# circuitplay_rev_G.net
KiCad netlist of a schematic drawn in EAGLE
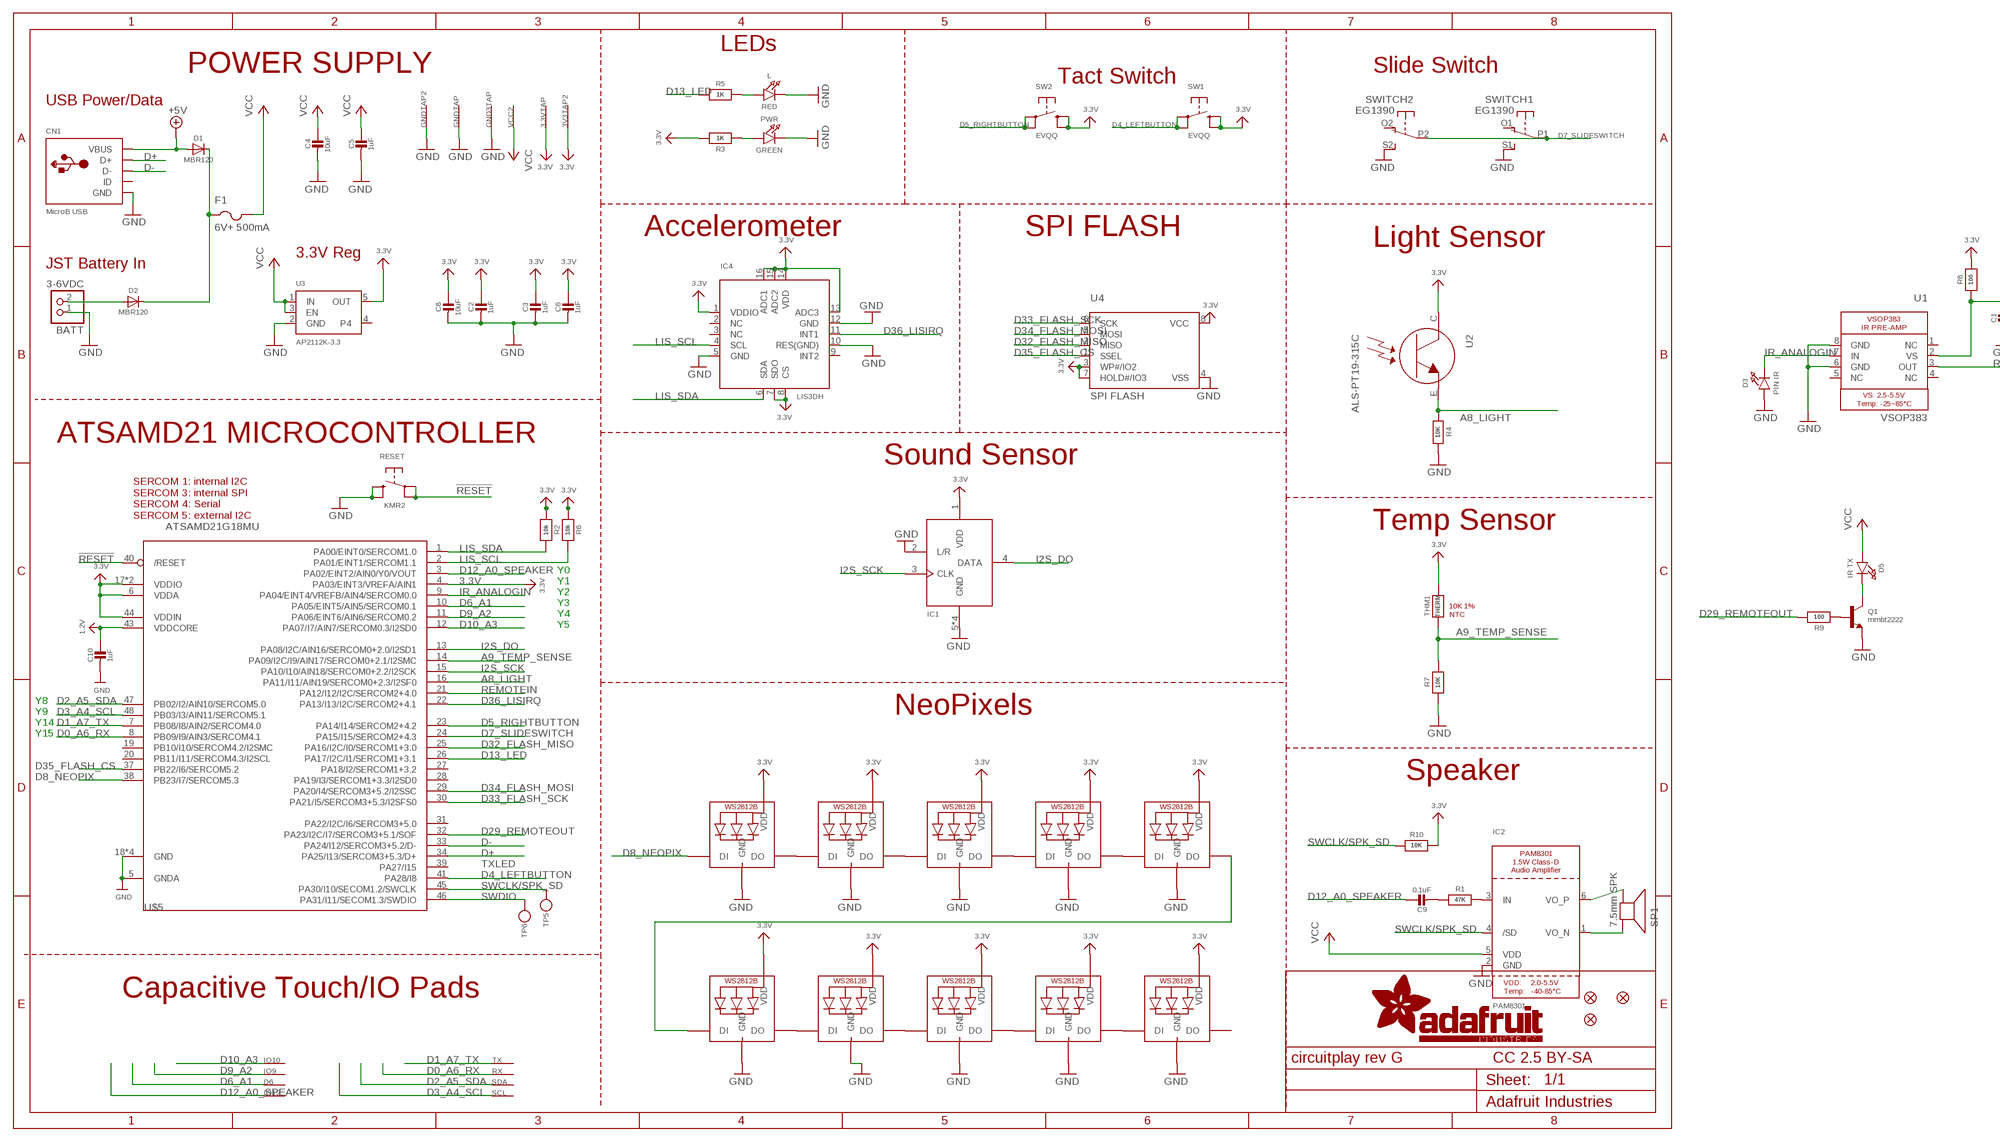
[diagram p0: schematic, sheet 1, part 1 of 2]
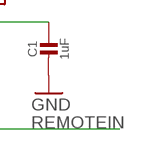
[diagram p1: schematic, sheet 1, part 2 of 2]

(export (version "E")
  (design (tool "Eeschema 10.0.6"))
  (components
    (comp (ref "3.3VTAP")
      (value "SEWTAP-ALLIGATOR")
      (footprint "eagle-import:SEWALLI")
      (libsource (lib "eagle-import") (part "SEWTAP-ALLIGATOR"))
    )
    (comp (ref "3V3TAP2")
      (value "SEWTAP-ALLIGATOR")
      (footprint "eagle-import:SEWALLI")
      (libsource (lib "eagle-import") (part "SEWTAP-ALLIGATOR"))
    )
    (comp (ref "BATT")
      (value "3-6VDC")
      (footprint "eagle-import:JSTPH2")
      (libsource (lib "eagle-import") (part "CON_JST_PH_2PIN"))
    )
    (comp (ref "C1")
      (value "1uF")
      (footprint "eagle-import:0603-NO")
      (libsource (lib "eagle-import") (part "CAP_CERAMIC0603_NO"))
    )
    (comp (ref "C2")
      (value "1uF")
      (footprint "eagle-import:0603-NO")
      (libsource (lib "eagle-import") (part "CAP_CERAMIC0603_NO"))
    )
    (comp (ref "C3")
      (value "1uF")
      (footprint "eagle-import:0603-NO")
      (libsource (lib "eagle-import") (part "CAP_CERAMIC0603_NO"))
    )
    (comp (ref "C4")
      (value "10uF")
      (footprint "eagle-import:0805-NO")
      (libsource (lib "eagle-import") (part "CAP_CERAMIC0805-NOOUTLINE"))
    )
    (comp (ref "C5")
      (value "1uF")
      (footprint "eagle-import:0603-NO")
      (libsource (lib "eagle-import") (part "CAP_CERAMIC0603_NO"))
    )
    (comp (ref "C6")
      (value "1uF")
      (footprint "eagle-import:0603-NO")
      (libsource (lib "eagle-import") (part "CAP_CERAMIC0603_NO"))
    )
    (comp (ref "C8")
      (value "10uF")
      (footprint "eagle-import:0805-NO")
      (libsource (lib "eagle-import") (part "CAP_CERAMIC0805-NOOUTLINE"))
    )
    (comp (ref "C9")
      (value "0.1uF")
      (footprint "eagle-import:0603-NO")
      (libsource (lib "eagle-import") (part "CAP_CERAMIC0603_NO"))
    )
    (comp (ref "C10")
      (value "1uF")
      (footprint "eagle-import:0603-NO")
      (libsource (lib "eagle-import") (part "CAP_CERAMIC0603_NO"))
    )
    (comp (ref "CN1")
      (value "MicroB USB")
      (footprint "eagle-import:4UCONN_20329_V2")
      (libsource (lib "eagle-import") (part "USB_MICRO_20329_V2"))
    )
    (comp (ref "D1")
      (value "MBR120")
      (footprint "eagle-import:SOD-123")
      (libsource (lib "eagle-import") (part "DIODESOD-123"))
    )
    (comp (ref "D2")
      (value "MBR120")
      (footprint "eagle-import:SOD-123")
      (libsource (lib "eagle-import") (part "DIODESOD-123"))
    )
    (comp (ref "D3")
      (value "PIN IR")
      (footprint "eagle-import:CHIPLED_1206_NOOUTLINE")
      (libsource (lib "eagle-import") (part "LED1206_NOOUTLINE"))
    )
    (comp (ref "D5")
      (value "IR TX")
      (footprint "eagle-import:CHIPLED_1206_NOOUTLINE")
      (libsource (lib "eagle-import") (part "LED1206_NOOUTLINE"))
    )
    (comp (ref "D6")
      (value "SEWTAP-ALLIGATOR")
      (footprint "eagle-import:SEWALLI")
      (libsource (lib "eagle-import") (part "SEWTAP-ALLIGATOR"))
    )
    (comp (ref "F1")
      (value "6V+ 500mA")
      (footprint "eagle-import:R1206")
      (libsource (lib "eagle-import") (part "PTCFUSE-1206"))
    )
    (comp (ref "GND3TAP")
      (value "SEWTAP-ALLIGATOR")
      (footprint "eagle-import:SEWALLI")
      (libsource (lib "eagle-import") (part "SEWTAP-ALLIGATOR"))
    )
    (comp (ref "GNDTAP")
      (value "SEWTAP-ALLIGATOR")
      (footprint "eagle-import:SEWALLI")
      (libsource (lib "eagle-import") (part "SEWTAP-ALLIGATOR"))
    )
    (comp (ref "GNDTAP2")
      (value "SEWTAP-ALLIGATOR")
      (footprint "eagle-import:SEWALLI")
      (libsource (lib "eagle-import") (part "SEWTAP-ALLIGATOR"))
    )
    (comp (ref "IC1")
      (value "MIC_PDM")
      (footprint "eagle-import:SPK0415HM4H")
      (libsource (lib "eagle-import") (part "MIC_PDM_SPK0415"))
    )
    (comp (ref "IC2")
      (value "PAM8301")
      (footprint "eagle-import:SOT23-6")
      (libsource (lib "eagle-import") (part "PAM8301"))
    )
    (comp (ref "IC4")
      (value "LIS3DH")
      (footprint "eagle-import:LGA16_3X3MM")
      (libsource (lib "eagle-import") (part "ACCEL_LIS3DHTR"))
    )
    (comp (ref "IO9")
      (value "SEWTAP-ALLIGATOR")
      (footprint "eagle-import:SEWALLI")
      (libsource (lib "eagle-import") (part "SEWTAP-ALLIGATOR"))
    )
    (comp (ref "IO10")
      (value "SEWTAP-ALLIGATOR")
      (footprint "eagle-import:SEWALLI")
      (libsource (lib "eagle-import") (part "SEWTAP-ALLIGATOR"))
    )
    (comp (ref "IO12")
      (value "SEWTAP-ALLIGATOR")
      (footprint "eagle-import:SEWALLI")
      (libsource (lib "eagle-import") (part "SEWTAP-ALLIGATOR"))
    )
    (comp (ref "L")
      (value "RED")
      (footprint "eagle-import:CHIPLED_0805_NOOUTLINE")
      (libsource (lib "eagle-import") (part "LED0805_NOOUTLINE"))
    )
    (comp (ref "LED1")
      (value "WS2812B3535")
      (footprint "eagle-import:LED3535")
      (libsource (lib "eagle-import") (part "WS2812B3535"))
    )
    (comp (ref "LED2")
      (value "WS2812B3535")
      (footprint "eagle-import:LED3535")
      (libsource (lib "eagle-import") (part "WS2812B3535"))
    )
    (comp (ref "LED3")
      (value "WS2812B3535")
      (footprint "eagle-import:LED3535")
      (libsource (lib "eagle-import") (part "WS2812B3535"))
    )
    (comp (ref "LED4")
      (value "WS2812B3535")
      (footprint "eagle-import:LED3535")
      (libsource (lib "eagle-import") (part "WS2812B3535"))
    )
    (comp (ref "LED5")
      (value "WS2812B3535")
      (footprint "eagle-import:LED3535")
      (libsource (lib "eagle-import") (part "WS2812B3535"))
    )
    (comp (ref "LED6")
      (value "WS2812B3535")
      (footprint "eagle-import:LED3535")
      (libsource (lib "eagle-import") (part "WS2812B3535"))
    )
    (comp (ref "LED7")
      (value "WS2812B3535")
      (footprint "eagle-import:LED3535")
      (libsource (lib "eagle-import") (part "WS2812B3535"))
    )
    (comp (ref "LED8")
      (value "WS2812B3535")
      (footprint "eagle-import:LED3535")
      (libsource (lib "eagle-import") (part "WS2812B3535"))
    )
    (comp (ref "LED9")
      (value "WS2812B3535")
      (footprint "eagle-import:LED3535")
      (libsource (lib "eagle-import") (part "WS2812B3535"))
    )
    (comp (ref "LED10")
      (value "WS2812B3535")
      (footprint "eagle-import:LED3535")
      (libsource (lib "eagle-import") (part "WS2812B3535"))
    )
    (comp (ref "PWR")
      (value "GREEN")
      (footprint "eagle-import:CHIPLED_0805_NOOUTLINE")
      (libsource (lib "eagle-import") (part "LED0805_NOOUTLINE"))
    )
    (comp (ref "Q1")
      (value "mmbt2222")
      (footprint "eagle-import:SOT23-R")
      (libsource (lib "eagle-import") (part "TRANSISTOR_NPN"))
    )
    (comp (ref "R1")
      (value "47K")
      (footprint "eagle-import:0603-NO")
      (libsource (lib "eagle-import") (part "RESISTOR_0603_NOOUT"))
    )
    (comp (ref "R2")
      (value "10k")
      (footprint "eagle-import:0603-NO")
      (libsource (lib "eagle-import") (part "RESISTOR_0603_NOOUT"))
    )
    (comp (ref "R3")
      (value "1K")
      (footprint "eagle-import:0603-NO")
      (libsource (lib "eagle-import") (part "RESISTOR_0603_NOOUT"))
    )
    (comp (ref "R4")
      (value "10K")
      (footprint "eagle-import:0603-NO")
      (libsource (lib "eagle-import") (part "RESISTOR_0603_NOOUT"))
    )
    (comp (ref "R5")
      (value "1K")
      (footprint "eagle-import:0603-NO")
      (libsource (lib "eagle-import") (part "RESISTOR_0603_NOOUT"))
    )
    (comp (ref "R6")
      (value "10k")
      (footprint "eagle-import:0603-NO")
      (libsource (lib "eagle-import") (part "RESISTOR_0603_NOOUT"))
    )
    (comp (ref "R7")
      (value "10K")
      (footprint "eagle-import:0603-NO")
      (libsource (lib "eagle-import") (part "RESISTOR_0603_NOOUT"))
    )
    (comp (ref "R8")
      (value "100")
      (footprint "eagle-import:0603-NO")
      (libsource (lib "eagle-import") (part "RESISTOR_0603_NOOUT"))
    )
    (comp (ref "R9")
      (value "100")
      (footprint "eagle-import:0603-NO")
      (libsource (lib "eagle-import") (part "RESISTOR_0603_NOOUT"))
    )
    (comp (ref "R10")
      (value "10K")
      (footprint "eagle-import:0603-NO")
      (libsource (lib "eagle-import") (part "RESISTOR_0603_NOOUT"))
    )
    (comp (ref "RESET")
      (value "KMR2")
      (footprint "eagle-import:BTN_KMR2_4.6X2.8")
      (libsource (lib "eagle-import") (part "SWITCH_TACT_SMT4.6X2.8"))
    )
    (comp (ref "RX")
      (value "SEWTAP-ALLIGATOR")
      (footprint "eagle-import:SEWALLI")
      (libsource (lib "eagle-import") (part "SEWTAP-ALLIGATOR"))
    )
    (comp (ref "SCL")
      (value "SEWTAP-ALLIGATOR")
      (footprint "eagle-import:SEWALLI")
      (libsource (lib "eagle-import") (part "SEWTAP-ALLIGATOR"))
    )
    (comp (ref "SDA")
      (value "SEWTAP-ALLIGATOR")
      (footprint "eagle-import:SEWALLI")
      (libsource (lib "eagle-import") (part "SEWTAP-ALLIGATOR"))
    )
    (comp (ref "SP1")
      (value "7.5mm SPK")
      (footprint "eagle-import:BUZZER_SMT_7.5MM")
      (libsource (lib "eagle-import") (part "SPEAKER_7.5MM"))
    )
    (comp (ref "SW1")
      (value "EVQQ")
      (footprint "eagle-import:EVQ-Q2_SMALLER")
      (libsource (lib "eagle-import") (part "SWITCH_TACT_SMT_EVQQ2_SMALL"))
    )
    (comp (ref "SW2")
      (value "EVQQ")
      (footprint "eagle-import:EVQ-Q2_SMALLER")
      (libsource (lib "eagle-import") (part "SWITCH_TACT_SMT_EVQQ2_SMALL"))
    )
    (comp (ref "SWITCH")
      (value "EG1390")
      (footprint "eagle-import:EG1390")
      (libsource (lib "eagle-import") (part "DPDT-EG1390"))
    )
    (comp (ref "THM1")
      (value "THERM")
      (footprint "eagle-import:_0402")
      (libsource (lib "eagle-import") (part "RESISTOR_0402"))
    )
    (comp (ref "TP5")
      (value "TESTPOINTROUND1.5MM")
      (footprint "eagle-import:TESTPOINT_ROUND_1.5MM")
      (libsource (lib "eagle-import") (part "TESTPOINTROUND1.5MM"))
    )
    (comp (ref "TP6")
      (value "TESTPOINTROUND1.5MM")
      (footprint "eagle-import:TESTPOINT_ROUND_1.5MM")
      (libsource (lib "eagle-import") (part "TESTPOINTROUND1.5MM"))
    )
    (comp (ref "TX")
      (value "SEWTAP-ALLIGATOR")
      (footprint "eagle-import:SEWALLI")
      (libsource (lib "eagle-import") (part "SEWTAP-ALLIGATOR"))
    )
    (comp (ref "U$2")
      (value "FIDUCIAL_1MM")
      (footprint "eagle-import:FIDUCIAL_1MM")
      (libsource (lib "eagle-import") (part "FIDUCIAL_1MM"))
    )
    (comp (ref "U$3")
      (value "FIDUCIAL_1MM")
      (footprint "eagle-import:FIDUCIAL_1MM")
      (fields (field (name "BOM") "EXCLUDE"))
      (libsource (lib "eagle-import") (part "FIDUCIAL_1MM"))
    )
    (comp (ref "U$5")
      (value "ATSAMD21G18MU")
      (footprint "eagle-import:TQFN48_7MM")
      (libsource (lib "eagle-import") (part "ATSAMD21G_QFN"))
    )
    (comp (ref "U$6")
      (value "FIDUCIAL_1MM")
      (footprint "eagle-import:FIDUCIAL_1MM")
      (libsource (lib "eagle-import") (part "FIDUCIAL_1MM"))
    )
    (comp (ref "U1")
      (value "VSOP383")
      (footprint "eagle-import:VSOP383")
      (libsource (lib "eagle-import") (part "VSOP383"))
    )
    (comp (ref "U2")
      (value "ALS-PT19-315C")
      (footprint "eagle-import:ALS-PT19-315C")
      (libsource (lib "eagle-import") (part "LIGHT_ALS-PT19-315C"))
    )
    (comp (ref "U3")
      (value "AP2112K-3.3")
      (footprint "eagle-import:SOT23-5")
      (libsource (lib "eagle-import") (part "VREG_SOT23-5"))
    )
    (comp (ref "U4")
      (value "SPI FLASH")
      (footprint "eagle-import:SOIC8_150MIL")
      (libsource (lib "eagle-import") (part "SPIFLASH_SOIC8"))
    )
    (comp (ref "VCC2")
      (value "SEWTAP-ALLIGATOR")
      (footprint "eagle-import:SEWALLI")
      (libsource (lib "eagle-import") (part "SEWTAP-ALLIGATOR"))
    )
  )
  (nets
    (net (code "1") (name "+5V") (class "Default")
      (node (ref "CN1") (pin "VBUS") (pinfunction "VBUS_VBUS") (pintype "power_in"))
      (node (ref "D1") (pin "A") (pinfunction "A_A") (pintype "passive"))
    )
    (net (code "2") (name "/A8_LIGHT") (class "Default")
      (node (ref "R4") (pin "2") (pinfunction "2_2") (pintype "passive"))
      (node (ref "U$5") (pin "16") (pinfunction "PA11/I11/AIN19/SERCOM0+2.3/I2SF0_16") (pintype "bidirectional"))
      (node (ref "U2") (pin "E") (pinfunction "E_E") (pintype "bidirectional"))
    )
    (net (code "3") (name "/A9_TEMP_SENSE") (class "Default")
      (node (ref "R7") (pin "2") (pinfunction "2_2") (pintype "passive"))
      (node (ref "THM1") (pin "1") (pinfunction "1_1") (pintype "passive"))
      (node (ref "U$5") (pin "14") (pinfunction "PA09/I2C/I9/AIN17/SERCOM0+2.1/I2SMC_14") (pintype "bidirectional"))
    )
    (net (code "4") (name "/D+") (class "Default")
      (node (ref "CN1") (pin "D+") (pinfunction "D+_D+") (pintype "bidirectional"))
      (node (ref "U$5") (pin "34") (pinfunction "PA25/I13/SERCOM3+5.3/D+_34") (pintype "bidirectional"))
    )
    (net (code "5") (name "/D-") (class "Default")
      (node (ref "CN1") (pin "D-") (pinfunction "D-_D-") (pintype "bidirectional"))
      (node (ref "U$5") (pin "33") (pinfunction "PA24/I12/SERCOM3+5.2/D-_33") (pintype "bidirectional"))
    )
    (net (code "6") (name "/D0_A6_RX") (class "Default")
      (node (ref "RX") (pin "P$1") (pinfunction "SEW_P$1") (pintype "bidirectional"))
      (node (ref "U$5") (pin "8") (pinfunction "PB09/I9/AIN3/SERCOM4.1_8") (pintype "bidirectional"))
    )
    (net (code "7") (name "/D1_A7_TX") (class "Default")
      (node (ref "TX") (pin "P$1") (pinfunction "SEW_P$1") (pintype "bidirectional"))
      (node (ref "U$5") (pin "7") (pinfunction "PB08/I8/AIN2/SERCOM4.0_7") (pintype "bidirectional"))
    )
    (net (code "8") (name "/D2_A5_SDA") (class "Default")
      (node (ref "SDA") (pin "P$1") (pinfunction "SEW_P$1") (pintype "bidirectional"))
      (node (ref "U$5") (pin "47") (pinfunction "PB02/I2/AIN10/SERCOM5.0_47") (pintype "bidirectional"))
    )
    (net (code "9") (name "/D3_A4_SCL") (class "Default")
      (node (ref "SCL") (pin "P$1") (pinfunction "SEW_P$1") (pintype "bidirectional"))
      (node (ref "U$5") (pin "48") (pinfunction "PB03/I3/AIN11/SERCOM5.1_48") (pintype "bidirectional"))
    )
    (net (code "10") (name "/D4_LEFTBUTTON") (class "Default")
      (node (ref "SW1") (pin "A") (pinfunction "P_A") (pintype "passive"))
      (node (ref "SW1") (pin "A'") (pinfunction "P1_A'") (pintype "passive"))
      (node (ref "U$5") (pin "41") (pinfunction "PA28/I8_41") (pintype "bidirectional"))
    )
    (net (code "11") (name "/D5_RIGHTBUTTON") (class "Default")
      (node (ref "SW2") (pin "A") (pinfunction "P_A") (pintype "passive"))
      (node (ref "SW2") (pin "A'") (pinfunction "P1_A'") (pintype "passive"))
      (node (ref "U$5") (pin "23") (pinfunction "PA14/I14/SERCOM2+4.2_23") (pintype "bidirectional"))
    )
    (net (code "12") (name "/D6_A1") (class "Default")
      (node (ref "D6") (pin "P$1") (pinfunction "SEW_P$1") (pintype "bidirectional"))
      (node (ref "U$5") (pin "10") (pinfunction "PA05/EINT5/AIN5/SERCOM0.1_10") (pintype "bidirectional"))
    )
    (net (code "13") (name "/D7_SLIDESWITCH") (class "Default")
      (node (ref "SWITCH") (pin "P1") (pinfunction "P_P1") (pintype "passive"))
      (node (ref "SWITCH") (pin "P2") (pinfunction "P_P2") (pintype "passive"))
      (node (ref "U$5") (pin "24") (pinfunction "PA15/I15/SERCOM2+4.3_24") (pintype "bidirectional"))
    )
    (net (code "14") (name "/D8_NEOPIX") (class "Default")
      (node (ref "LED6") (pin "1") (pinfunction "DI_1") (pintype "input"))
      (node (ref "U$5") (pin "38") (pinfunction "PB23/I7/SERCOM5.3_38") (pintype "bidirectional"))
    )
    (net (code "15") (name "/D9_A2") (class "Default")
      (node (ref "IO9") (pin "P$1") (pinfunction "SEW_P$1") (pintype "bidirectional"))
      (node (ref "U$5") (pin "11") (pinfunction "PA06/EINT6/AIN6/SERCOM0.2_11") (pintype "bidirectional"))
    )
    (net (code "16") (name "/D10_A3") (class "Default")
      (node (ref "IO10") (pin "P$1") (pinfunction "SEW_P$1") (pintype "bidirectional"))
      (node (ref "U$5") (pin "12") (pinfunction "PA07/I7/AIN7/SERCOM0.3/I2SD0_12") (pintype "bidirectional"))
    )
    (net (code "17") (name "/D12_A0_SPEAKER") (class "Default")
      (node (ref "C9") (pin "1") (pinfunction "1_1") (pintype "passive"))
      (node (ref "IO12") (pin "P$1") (pinfunction "SEW_P$1") (pintype "bidirectional"))
      (node (ref "U$5") (pin "3") (pinfunction "PA02/EINT2/AIN0/Y0/VOUT_3") (pintype "bidirectional"))
    )
    (net (code "18") (name "/D13_LED") (class "Default")
      (node (ref "R5") (pin "1") (pinfunction "1_1") (pintype "passive"))
      (node (ref "U$5") (pin "26") (pinfunction "PA17/I2C/I1/SERCOM1+3.1_26") (pintype "bidirectional"))
    )
    (net (code "19") (name "/D29_REMOTEOUT") (class "Default")
      (node (ref "R9") (pin "2") (pinfunction "2_2") (pintype "passive"))
      (node (ref "U$5") (pin "32") (pinfunction "PA23/I2C/I7/SERCOM3+5.1/SOF_32") (pintype "bidirectional"))
    )
    (net (code "20") (name "/D32_FLASH_MISO") (class "Default")
      (node (ref "U$5") (pin "25") (pinfunction "PA16/I2C/I0/SERCOM1+3.0_25") (pintype "bidirectional"))
      (node (ref "U4") (pin "2") (pinfunction "MISO_2") (pintype "bidirectional"))
    )
    (net (code "21") (name "/D33_FLASH_SCK") (class "Default")
      (node (ref "U$5") (pin "30") (pinfunction "PA21/I5/SERCOM3+5.3/I2SFS0_30") (pintype "bidirectional"))
      (node (ref "U4") (pin "6") (pinfunction "SCK_6") (pintype "bidirectional"))
    )
    (net (code "22") (name "/D34_FLASH_MOSI") (class "Default")
      (node (ref "U$5") (pin "29") (pinfunction "PA20/I4/SERCOM3+5.2/I2SSC_29") (pintype "bidirectional"))
      (node (ref "U4") (pin "5") (pinfunction "MOSI_5") (pintype "bidirectional"))
    )
    (net (code "23") (name "/D35_FLASH_CS") (class "Default")
      (node (ref "U$5") (pin "37") (pinfunction "PB22/I6/SERCOM5.2_37") (pintype "bidirectional"))
      (node (ref "U4") (pin "1") (pinfunction "SSEL_1") (pintype "bidirectional"))
    )
    (net (code "24") (name "/D36_LISIRQ") (class "Default")
      (node (ref "IC4") (pin "11") (pinfunction "INT1_11") (pintype "output"))
      (node (ref "U$5") (pin "22") (pinfunction "PA13/I13/I2C/SERCOM2+4.1_22") (pintype "bidirectional"))
    )
    (net (code "25") (name "/I2S_DO") (class "Default")
      (node (ref "IC1") (pin "4") (pinfunction "DATA_4") (pintype "bidirectional"))
      (node (ref "U$5") (pin "13") (pinfunction "PA08/I2C/AIN16/SERCOM0+2.0/I2SD1_13") (pintype "bidirectional"))
    )
    (net (code "26") (name "/I2S_SCK") (class "Default")
      (node (ref "IC1") (pin "3") (pinfunction "CLK_3") (pintype "input"))
      (node (ref "U$5") (pin "15") (pinfunction "PA10/I10/AIN18/SERCOM0+2.2/I2SCK_15") (pintype "bidirectional"))
    )
    (net (code "27") (name "/IR_ANALOGIN") (class "Default")
      (node (ref "D3") (pin "C") (pinfunction "C_C") (pintype "passive"))
      (node (ref "U$5") (pin "9") (pinfunction "PA04/EINT4/VREFB/AIN4/SERCOM0.0_9") (pintype "bidirectional"))
      (node (ref "U1") (pin "7") (pinfunction "IN_7") (pintype "input"))
    )
    (net (code "28") (name "/LIS_SCL") (class "Default")
      (node (ref "IC4") (pin "4") (pinfunction "SCL_4") (pintype "bidirectional"))
      (node (ref "R6") (pin "2") (pinfunction "2_2") (pintype "passive"))
      (node (ref "U$5") (pin "2") (pinfunction "PA01/EINT1/SERCOM1.1_2") (pintype "bidirectional"))
    )
    (net (code "29") (name "/LIS_SDA") (class "Default")
      (node (ref "IC4") (pin "6") (pinfunction "SDA_6") (pintype "bidirectional"))
      (node (ref "R2") (pin "2") (pinfunction "2_2") (pintype "passive"))
      (node (ref "U$5") (pin "1") (pinfunction "PA00/EINT0/SERCOM1.0_1") (pintype "bidirectional"))
    )
    (net (code "30") (name "/REMOTEIN") (class "Default")
      (node (ref "U$5") (pin "21") (pinfunction "PA12/I12/I2C/SERCOM2+4.0_21") (pintype "bidirectional"))
      (node (ref "U1") (pin "3") (pinfunction "OUT_3") (pintype "output"))
    )
    (net (code "31") (name "/SWCLK{slash}SPK_SD") (class "Default")
      (node (ref "IC2") (pin "4") (pinfunction "/SD_4") (pintype "input"))
      (node (ref "R10") (pin "1") (pinfunction "1_1") (pintype "passive"))
      (node (ref "TP5") (pin "P$1") (pinfunction "P$1_P$1") (pintype "bidirectional"))
      (node (ref "U$5") (pin "45") (pinfunction "PA30/I10/SECOM1.2/SWCLK_45") (pintype "bidirectional"))
    )
    (net (code "32") (name "/SWDIO") (class "Default")
      (node (ref "TP6") (pin "P$1") (pinfunction "P$1_P$1") (pintype "bidirectional"))
      (node (ref "U$5") (pin "46") (pinfunction "PA31/I11/SECOM1.3/SWDIO_46") (pintype "bidirectional"))
    )
    (net (code "33") (name "/~{RESET}") (class "Default")
      (node (ref "RESET") (pin "A") (pinfunction "P_A") (pintype "passive"))
      (node (ref "RESET") (pin "A'") (pinfunction "P1_A'") (pintype "passive"))
      (node (ref "U$5") (pin "40") (pinfunction "/RESET_40") (pintype "bidirectional"))
    )
    (net (code "34") (name "1.2V") (class "Default")
      (node (ref "C10") (pin "1") (pinfunction "1_1") (pintype "passive"))
      (node (ref "U$5") (pin "43") (pinfunction "VDDCORE_43") (pintype "power_in"))
    )
    (net (code "35") (name "3.3V") (class "Default")
      (node (ref "3.3VTAP") (pin "P$1") (pinfunction "SEW_P$1") (pintype "bidirectional"))
      (node (ref "3V3TAP2") (pin "P$1") (pinfunction "SEW_P$1") (pintype "bidirectional"))
      (node (ref "C2") (pin "1") (pinfunction "1_1") (pintype "passive"))
      (node (ref "C3") (pin "1") (pinfunction "1_1") (pintype "passive"))
      (node (ref "C6") (pin "1") (pinfunction "1_1") (pintype "passive"))
      (node (ref "C8") (pin "1") (pinfunction "1_1") (pintype "passive"))
      (node (ref "IC1") (pin "1") (pinfunction "VDD_1") (pintype "power_in"))
      (node (ref "IC4") (pin "1") (pinfunction "VDDIO_1") (pintype "power_in"))
      (node (ref "IC4") (pin "13") (pinfunction "ADC3_13") (pintype "input"))
      (node (ref "IC4") (pin "14") (pinfunction "VDD_14") (pintype "power_in"))
      (node (ref "IC4") (pin "15") (pinfunction "ADC2_15") (pintype "input"))
      (node (ref "IC4") (pin "16") (pinfunction "ADC1_16") (pintype "input"))
      (node (ref "IC4") (pin "7") (pinfunction "SDO_7") (pintype "bidirectional"))
      (node (ref "IC4") (pin "8") (pinfunction "CS_8") (pintype "input"))
      (node (ref "LED1") (pin "2") (pinfunction "VDD_2") (pintype "power_in"))
      (node (ref "LED10") (pin "2") (pinfunction "VDD_2") (pintype "power_in"))
      (node (ref "LED2") (pin "2") (pinfunction "VDD_2") (pintype "power_in"))
      (node (ref "LED3") (pin "2") (pinfunction "VDD_2") (pintype "power_in"))
      (node (ref "LED4") (pin "2") (pinfunction "VDD_2") (pintype "power_in"))
      (node (ref "LED5") (pin "2") (pinfunction "VDD_2") (pintype "power_in"))
      (node (ref "LED6") (pin "2") (pinfunction "VDD_2") (pintype "power_in"))
      (node (ref "LED7") (pin "2") (pinfunction "VDD_2") (pintype "power_in"))
      (node (ref "LED8") (pin "2") (pinfunction "VDD_2") (pintype "power_in"))
      (node (ref "LED9") (pin "2") (pinfunction "VDD_2") (pintype "power_in"))
      (node (ref "R10") (pin "2") (pinfunction "2_2") (pintype "passive"))
      (node (ref "R2") (pin "1") (pinfunction "1_1") (pintype "passive"))
      (node (ref "R3") (pin "2") (pinfunction "2_2") (pintype "passive"))
      (node (ref "R6") (pin "1") (pinfunction "1_1") (pintype "passive"))
      (node (ref "R8") (pin "2") (pinfunction "2_2") (pintype "passive"))
      (node (ref "SW1") (pin "B") (pinfunction "S_B") (pintype "passive"))
      (node (ref "SW1") (pin "B'") (pinfunction "S1_B'") (pintype "passive"))
      (node (ref "SW2") (pin "B") (pinfunction "S_B") (pintype "passive"))
      (node (ref "SW2") (pin "B'") (pinfunction "S1_B'") (pintype "passive"))
      (node (ref "THM1") (pin "2") (pinfunction "2_2") (pintype "passive"))
      (node (ref "U$5") (pin "17") (pinfunction "VDDIO_17") (pintype "power_in"))
      (node (ref "U$5") (pin "36") (pinfunction "VDDIO_36") (pintype "power_in"))
      (node (ref "U$5") (pin "4") (pinfunction "PA03/EINT3/VREFA/AIN1_4") (pintype "bidirectional"))
      (node (ref "U$5") (pin "44") (pinfunction "VDDIN_44") (pintype "power_in"))
      (node (ref "U$5") (pin "6") (pinfunction "VDDA_6") (pintype "power_in"))
      (node (ref "U2") (pin "C") (pinfunction "C_C") (pintype "bidirectional"))
      (node (ref "U3") (pin "5") (pinfunction "OUT_5") (pintype "power_in"))
      (node (ref "U4") (pin "3") (pinfunction "WP#/IO2_3") (pintype "bidirectional"))
      (node (ref "U4") (pin "7") (pinfunction "HOLD#/IO3_7") (pintype "bidirectional"))
      (node (ref "U4") (pin "8") (pinfunction "VCC_8") (pintype "bidirectional"))
    )
    (net (code "36") (name "GND") (class "Default")
      (node (ref "BATT") (pin "1") (pinfunction "1_1") (pintype "passive"))
      (node (ref "C1") (pin "2") (pinfunction "2_2") (pintype "passive"))
      (node (ref "C10") (pin "2") (pinfunction "2_2") (pintype "passive"))
      (node (ref "C2") (pin "2") (pinfunction "2_2") (pintype "passive"))
      (node (ref "C3") (pin "2") (pinfunction "2_2") (pintype "passive"))
      (node (ref "C4") (pin "2") (pinfunction "2_2") (pintype "passive"))
      (node (ref "C5") (pin "2") (pinfunction "2_2") (pintype "passive"))
      (node (ref "C6") (pin "2") (pinfunction "2_2") (pintype "passive"))
      (node (ref "C8") (pin "2") (pinfunction "2_2") (pintype "passive"))
      (node (ref "CN1") (pin "BASE@1") (pinfunction "GND_BASE@1") (pintype "power_in"))
      (node (ref "CN1") (pin "BASE@2") (pinfunction "GND_BASE@2") (pintype "power_in"))
      (node (ref "CN1") (pin "GND") (pinfunction "GND_GND") (pintype "power_in"))
      (node (ref "CN1") (pin "SPRT@1") (pinfunction "GND_SPRT@1") (pintype "power_in"))
      (node (ref "CN1") (pin "SPRT@2") (pinfunction "GND_SPRT@2") (pintype "power_in"))
      (node (ref "CN1") (pin "SPRT@3") (pinfunction "GND_SPRT@3") (pintype "power_in"))
      (node (ref "CN1") (pin "SPRT@4") (pinfunction "GND_SPRT@4") (pintype "power_in"))
      (node (ref "D3") (pin "A") (pinfunction "A_A") (pintype "passive"))
      (node (ref "GND3TAP") (pin "P$1") (pinfunction "SEW_P$1") (pintype "bidirectional"))
      (node (ref "GNDTAP") (pin "P$1") (pinfunction "SEW_P$1") (pintype "bidirectional"))
      (node (ref "GNDTAP2") (pin "P$1") (pinfunction "SEW_P$1") (pintype "bidirectional"))
      (node (ref "IC1") (pin "2") (pinfunction "L/R_2") (pintype "input"))
      (node (ref "IC1") (pin "5") (pinfunction "GND_5") (pintype "power_in"))
      (node (ref "IC1") (pin "6") (pinfunction "GND_6") (pintype "power_in"))
      (node (ref "IC1") (pin "7") (pinfunction "GND_7") (pintype "power_in"))
      (node (ref "IC1") (pin "8") (pinfunction "GND_8") (pintype "power_in"))
      (node (ref "IC2") (pin "2") (pinfunction "GND_2") (pintype "power_in"))
      (node (ref "IC4") (pin "10") (pinfunction "RES(GND)_10") (pintype "bidirectional"))
      (node (ref "IC4") (pin "12") (pinfunction "GND_12") (pintype "power_in"))
      (node (ref "IC4") (pin "5") (pinfunction "GND_5") (pintype "power_in"))
      (node (ref "L") (pin "C") (pinfunction "C_C") (pintype "passive"))
      (node (ref "LED1") (pin "4") (pinfunction "GND_4") (pintype "power_in"))
      (node (ref "LED10") (pin "4") (pinfunction "GND_4") (pintype "power_in"))
      (node (ref "LED2") (pin "4") (pinfunction "GND_4") (pintype "power_in"))
      (node (ref "LED3") (pin "4") (pinfunction "GND_4") (pintype "power_in"))
      (node (ref "LED4") (pin "4") (pinfunction "GND_4") (pintype "power_in"))
      (node (ref "LED5") (pin "4") (pinfunction "GND_4") (pintype "power_in"))
      (node (ref "LED6") (pin "4") (pinfunction "GND_4") (pintype "power_in"))
      (node (ref "LED7") (pin "4") (pinfunction "GND_4") (pintype "power_in"))
      (node (ref "LED8") (pin "4") (pinfunction "GND_4") (pintype "power_in"))
      (node (ref "LED9") (pin "4") (pinfunction "GND_4") (pintype "power_in"))
      (node (ref "PWR") (pin "C") (pinfunction "C_C") (pintype "passive"))
      (node (ref "Q1") (pin "2") (pinfunction "E_2") (pintype "passive"))
      (node (ref "R4") (pin "1") (pinfunction "1_1") (pintype "passive"))
      (node (ref "R7") (pin "1") (pinfunction "1_1") (pintype "passive"))
      (node (ref "RESET") (pin "B") (pinfunction "S_B") (pintype "passive"))
      (node (ref "RESET") (pin "B'") (pinfunction "S1_B'") (pintype "passive"))
      (node (ref "SWITCH") (pin "S1") (pinfunction "S_S1") (pintype "passive"))
      (node (ref "SWITCH") (pin "S2") (pinfunction "S_S2") (pintype "passive"))
      (node (ref "U$5") (pin "18") (pinfunction "GND_18") (pintype "power_in"))
      (node (ref "U$5") (pin "35") (pinfunction "GND_35") (pintype "power_in"))
      (node (ref "U$5") (pin "42") (pinfunction "GND_42") (pintype "power_in"))
      (node (ref "U$5") (pin "5") (pinfunction "GNDA_5") (pintype "power_in"))
      (node (ref "U$5") (pin "THERMAL") (pinfunction "GND_THERMAL") (pintype "power_in"))
      (node (ref "U1") (pin "6") (pinfunction "GND_6") (pintype "power_in"))
      (node (ref "U1") (pin "8") (pinfunction "GND_8") (pintype "power_in"))
      (node (ref "U3") (pin "2") (pinfunction "GND_2") (pintype "power_in"))
      (node (ref "U4") (pin "4") (pinfunction "VSS_4") (pintype "bidirectional"))
    )
    (net (code "37") (name "Net-(BATT-Pad2)") (class "Default")
      (node (ref "BATT") (pin "2") (pinfunction "2_2") (pintype "passive"))
      (node (ref "D2") (pin "A") (pinfunction "A_A") (pintype "passive"))
    )
    (net (code "38") (name "Net-(C9-Pad2)") (class "Default")
      (node (ref "C9") (pin "2") (pinfunction "2_2") (pintype "passive"))
      (node (ref "R1") (pin "1") (pinfunction "1_1") (pintype "passive"))
    )
    (net (code "39") (name "Net-(D1-PadC)") (class "Default")
      (node (ref "D1") (pin "C") (pinfunction "C_C") (pintype "passive"))
      (node (ref "D2") (pin "C") (pinfunction "C_C") (pintype "passive"))
      (node (ref "F1") (pin "1") (pinfunction "1_1") (pintype "passive"))
    )
    (net (code "40") (name "Net-(IC2-IN)") (class "Default")
      (node (ref "IC2") (pin "3") (pinfunction "IN_3") (pintype "input"))
      (node (ref "R1") (pin "2") (pinfunction "2_2") (pintype "passive"))
    )
    (net (code "41") (name "Net-(IC2-VO_N)") (class "Default")
      (node (ref "IC2") (pin "1") (pinfunction "VO_N_1") (pintype "output"))
      (node (ref "SP1") (pin "+") (pinfunction "+_+") (pintype "passive"))
    )
    (net (code "42") (name "Net-(IC2-VO_P)") (class "Default")
      (node (ref "IC2") (pin "6") (pinfunction "VO_P_6") (pintype "output"))
      (node (ref "SP1") (pin "-") (pinfunction "-_-") (pintype "passive"))
    )
    (net (code "43") (name "Net-(L-PadA)") (class "Default")
      (node (ref "L") (pin "A") (pinfunction "A_A") (pintype "passive"))
      (node (ref "R5") (pin "2") (pinfunction "2_2") (pintype "passive"))
    )
    (net (code "44") (name "Net-(LED1-DI)") (class "Default")
      (node (ref "LED1") (pin "1") (pinfunction "DI_1") (pintype "input"))
      (node (ref "LED2") (pin "3") (pinfunction "DO_3") (pintype "output"))
    )
    (net (code "45") (name "Net-(LED1-DO)") (class "Default")
      (node (ref "LED1") (pin "3") (pinfunction "DO_3") (pintype "output"))
      (node (ref "LED3") (pin "1") (pinfunction "DI_1") (pintype "input"))
    )
    (net (code "46") (name "Net-(LED3-DO)") (class "Default")
      (node (ref "LED3") (pin "3") (pinfunction "DO_3") (pintype "output"))
      (node (ref "LED4") (pin "1") (pinfunction "DI_1") (pintype "input"))
    )
    (net (code "47") (name "Net-(LED4-DO)") (class "Default")
      (node (ref "LED4") (pin "3") (pinfunction "DO_3") (pintype "output"))
      (node (ref "LED5") (pin "1") (pinfunction "DI_1") (pintype "input"))
    )
    (net (code "48") (name "Net-(LED6-DO)") (class "Default")
      (node (ref "LED6") (pin "3") (pinfunction "DO_3") (pintype "output"))
      (node (ref "LED7") (pin "1") (pinfunction "DI_1") (pintype "input"))
    )
    (net (code "49") (name "Net-(LED7-DO)") (class "Default")
      (node (ref "LED7") (pin "3") (pinfunction "DO_3") (pintype "output"))
      (node (ref "LED8") (pin "1") (pinfunction "DI_1") (pintype "input"))
    )
    (net (code "50") (name "Net-(LED8-DO)") (class "Default")
      (node (ref "LED8") (pin "3") (pinfunction "DO_3") (pintype "output"))
      (node (ref "LED9") (pin "1") (pinfunction "DI_1") (pintype "input"))
    )
    (net (code "51") (name "Net-(LED10-DI)") (class "Default")
      (node (ref "LED10") (pin "1") (pinfunction "DI_1") (pintype "input"))
      (node (ref "LED9") (pin "3") (pinfunction "DO_3") (pintype "output"))
    )
    (net (code "52") (name "Net-(LED10-DO)") (class "Default")
      (node (ref "LED10") (pin "3") (pinfunction "DO_3") (pintype "output"))
      (node (ref "LED2") (pin "1") (pinfunction "DI_1") (pintype "input"))
    )
    (net (code "53") (name "Net-(PWR-PadA)") (class "Default")
      (node (ref "PWR") (pin "A") (pinfunction "A_A") (pintype "passive"))
      (node (ref "R3") (pin "1") (pinfunction "1_1") (pintype "passive"))
    )
    (net (code "54") (name "Net-(Q1-B)") (class "Default")
      (node (ref "Q1") (pin "1") (pinfunction "B_1") (pintype "passive"))
      (node (ref "R9") (pin "1") (pinfunction "1_1") (pintype "passive"))
    )
    (net (code "55") (name "Net-(Q1-C)") (class "Default")
      (node (ref "D5") (pin "C") (pinfunction "C_C") (pintype "passive"))
      (node (ref "Q1") (pin "3") (pinfunction "C_3") (pintype "passive"))
    )
    (net (code "56") (name "Net-(U1-VS)") (class "Default")
      (node (ref "C1") (pin "1") (pinfunction "1_1") (pintype "passive"))
      (node (ref "R8") (pin "1") (pinfunction "1_1") (pintype "passive"))
      (node (ref "U1") (pin "2") (pinfunction "VS_2") (pintype "power_in"))
    )
    (net (code "57") (name "VCC") (class "Default")
      (node (ref "C4") (pin "1") (pinfunction "1_1") (pintype "passive"))
      (node (ref "C5") (pin "1") (pinfunction "1_1") (pintype "passive"))
      (node (ref "D5") (pin "A") (pinfunction "A_A") (pintype "passive"))
      (node (ref "F1") (pin "2") (pinfunction "2_2") (pintype "passive"))
      (node (ref "IC2") (pin "5") (pinfunction "VDD_5") (pintype "power_in"))
      (node (ref "U3") (pin "1") (pinfunction "IN_1") (pintype "power_in"))
      (node (ref "U3") (pin "3") (pinfunction "EN_3") (pintype "input"))
      (node (ref "VCC2") (pin "P$1") (pinfunction "SEW_P$1") (pintype "bidirectional"))
    )
    (net (code "58") (name "unconnected-(CN1-PadID)") (class "Default")
      (node (ref "CN1") (pin "ID") (pinfunction "ID_ID") (pintype "bidirectional"))
    )
    (net (code "59") (name "unconnected-(IC4-INT2-Pad9)") (class "Default")
      (node (ref "IC4") (pin "9") (pinfunction "INT2_9") (pintype "output"))
    )
    (net (code "60") (name "unconnected-(IC4-NC-Pad2)") (class "Default")
      (node (ref "IC4") (pin "2") (pinfunction "NC_2") (pintype "no_connect"))
    )
    (net (code "61") (name "unconnected-(IC4-NC-Pad3)") (class "Default")
      (node (ref "IC4") (pin "3") (pinfunction "NC_3") (pintype "no_connect"))
    )
    (net (code "62") (name "unconnected-(LED5-DO-Pad3)") (class "Default")
      (node (ref "LED5") (pin "3") (pinfunction "DO_3") (pintype "output"))
    )
    (net (code "63") (name "unconnected-(SWITCHA-O-PadO1)") (class "Default")
      (node (ref "SWITCH") (pin "O1") (pinfunction "O_O1") (pintype "passive"))
    )
    (net (code "64") (name "unconnected-(SWITCHB-O-PadO2)") (class "Default")
      (node (ref "SWITCH") (pin "O2") (pinfunction "O_O2") (pintype "passive"))
    )
    (net (code "65") (name "unconnected-(U$5-PA18{slash}I2{slash}SERCOM1+3.2-Pad27)") (class "Default")
      (node (ref "U$5") (pin "27") (pinfunction "PA18/I2/SERCOM1+3.2_27") (pintype "bidirectional"))
    )
    (net (code "66") (name "unconnected-(U$5-PA19{slash}I3{slash}SERCOM1+3.3{slash}I2SD0-Pad28)") (class "Default")
      (node (ref "U$5") (pin "28") (pinfunction "PA19/I3/SERCOM1+3.3/I2SD0_28") (pintype "bidirectional"))
    )
    (net (code "67") (name "unconnected-(U$5-PA22{slash}I2C{slash}I6{slash}SERCOM3+5.0-Pad31)") (class "Default")
      (node (ref "U$5") (pin "31") (pinfunction "PA22/I2C/I6/SERCOM3+5.0_31") (pintype "bidirectional"))
    )
    (net (code "68") (name "unconnected-(U$5-PA27{slash}I15-Pad39)") (class "Default")
      (node (ref "U$5") (pin "39") (pinfunction "PA27/I15_39") (pintype "bidirectional"))
    )
    (net (code "69") (name "unconnected-(U$5-PB10{slash}I10{slash}SERCOM4.2{slash}I2SMC-Pad19)") (class "Default")
      (node (ref "U$5") (pin "19") (pinfunction "PB10/I10/SERCOM4.2/I2SMC_19") (pintype "bidirectional"))
    )
    (net (code "70") (name "unconnected-(U$5-PB11{slash}I11{slash}SERCOM4.3{slash}I2SCL-Pad20)") (class "Default")
      (node (ref "U$5") (pin "20") (pinfunction "PB11/I11/SERCOM4.3/I2SCL_20") (pintype "bidirectional"))
    )
    (net (code "71") (name "unconnected-(U1-NC-Pad1)") (class "Default")
      (node (ref "U1") (pin "1") (pinfunction "NC_1") (pintype "no_connect"))
    )
    (net (code "72") (name "unconnected-(U1-NC-Pad4)") (class "Default")
      (node (ref "U1") (pin "4") (pinfunction "NC_4") (pintype "no_connect"))
    )
    (net (code "73") (name "unconnected-(U1-NC-Pad5)") (class "Default")
      (node (ref "U1") (pin "5") (pinfunction "NC_5") (pintype "no_connect"))
    )
    (net (code "74") (name "unconnected-(U3-P4-Pad4)") (class "Default")
      (node (ref "U3") (pin "4") (pinfunction "P4_4") (pintype "bidirectional"))
    )
  )
)
